# MCU.net
KiCad netlist of a schematic drawn in Altium Designer
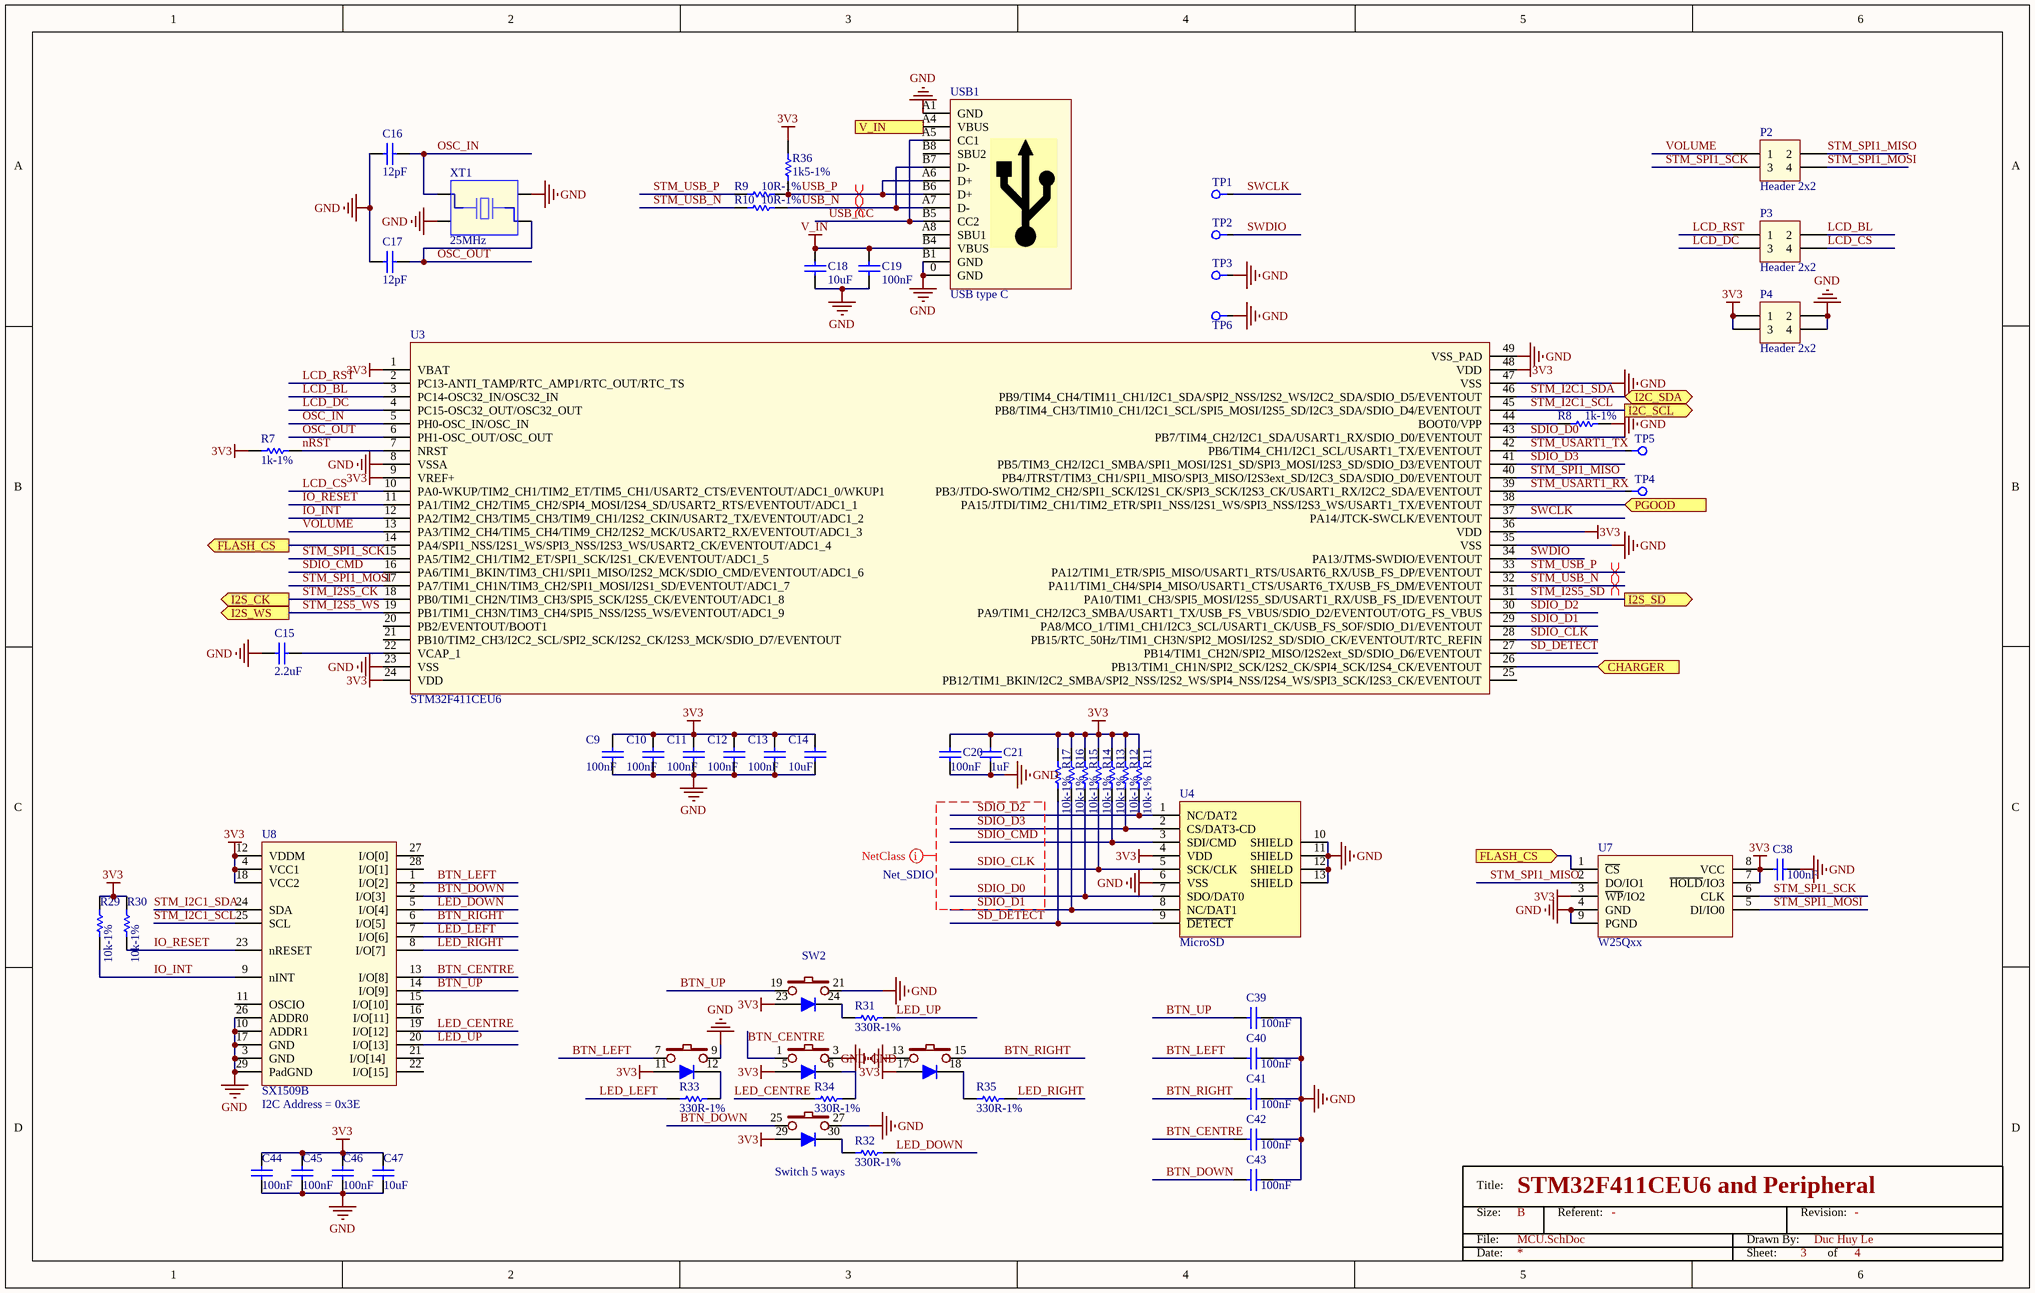
[diagram p0: MCU.SchDoc]

(export (version "E")
  (design (tool "Eeschema 10.0.6"))
  (components
    (comp (ref "C9")
      (value "100nF")
      (footprint "Cap 0603")
      (description "Cap SMD")
      (libsource (lib "duchuylee") (part "Cap"))
    )
    (comp (ref "C10")
      (value "100nF")
      (footprint "Cap 0603")
      (description "Cap SMD")
      (libsource (lib "duchuylee") (part "Cap"))
    )
    (comp (ref "C11")
      (value "100nF")
      (footprint "Cap 0603")
      (description "Cap SMD")
      (libsource (lib "duchuylee") (part "Cap"))
    )
    (comp (ref "C12")
      (value "100nF")
      (footprint "Cap 0603")
      (description "Cap SMD")
      (libsource (lib "duchuylee") (part "Cap"))
    )
    (comp (ref "C13")
      (value "100nF")
      (footprint "Cap 0603")
      (description "Cap SMD")
      (libsource (lib "duchuylee") (part "Cap"))
    )
    (comp (ref "C14")
      (value "10uF")
      (footprint "Cap 0603")
      (description "Cap SMD")
      (libsource (lib "duchuylee") (part "Cap"))
    )
    (comp (ref "C15")
      (value "2.2uF")
      (footprint "Cap 0603")
      (description "Cap SMD")
      (libsource (lib "duchuylee") (part "Cap"))
    )
    (comp (ref "C16")
      (value "12pF")
      (footprint "Cap 0603")
      (description "Cap SMD")
      (libsource (lib "duchuylee") (part "Cap"))
    )
    (comp (ref "C17")
      (value "12pF")
      (footprint "Cap 0603")
      (description "Cap SMD")
      (libsource (lib "duchuylee") (part "Cap"))
    )
    (comp (ref "C18")
      (value "10uF")
      (footprint "Cap 0603")
      (description "Cap SMD")
      (libsource (lib "duchuylee") (part "Cap"))
    )
    (comp (ref "C19")
      (value "100nF")
      (footprint "Cap 0603")
      (description "Cap SMD")
      (libsource (lib "duchuylee") (part "Cap"))
    )
    (comp (ref "C20")
      (value "100nF")
      (footprint "Cap 0603")
      (description "Cap SMD")
      (libsource (lib "duchuylee") (part "Cap"))
    )
    (comp (ref "C21")
      (value "1uF")
      (footprint "Cap 0603")
      (description "Cap SMD")
      (libsource (lib "duchuylee") (part "Cap"))
    )
    (comp (ref "C38")
      (value "100nF")
      (footprint "Cap 0603")
      (description "Cap SMD")
      (libsource (lib "duchuylee") (part "Cap"))
    )
    (comp (ref "C39")
      (value "100nF")
      (footprint "Cap 0603")
      (description "Cap SMD")
      (libsource (lib "duchuylee") (part "Cap"))
    )
    (comp (ref "C40")
      (value "100nF")
      (footprint "Cap 0603")
      (description "Cap SMD")
      (libsource (lib "duchuylee") (part "Cap"))
    )
    (comp (ref "C41")
      (value "100nF")
      (footprint "Cap 0603")
      (description "Cap SMD")
      (libsource (lib "duchuylee") (part "Cap"))
    )
    (comp (ref "C42")
      (value "100nF")
      (footprint "Cap 0603")
      (description "Cap SMD")
      (libsource (lib "duchuylee") (part "Cap"))
    )
    (comp (ref "C43")
      (value "100nF")
      (footprint "Cap 0603")
      (description "Cap SMD")
      (libsource (lib "duchuylee") (part "Cap"))
    )
    (comp (ref "C44")
      (value "100nF")
      (footprint "Cap 0603")
      (description "Cap SMD")
      (libsource (lib "duchuylee") (part "Cap"))
    )
    (comp (ref "C45")
      (value "100nF")
      (footprint "Cap 0603")
      (description "Cap SMD")
      (libsource (lib "duchuylee") (part "Cap"))
    )
    (comp (ref "C46")
      (value "100nF")
      (footprint "Cap 0603")
      (description "Cap SMD")
      (libsource (lib "duchuylee") (part "Cap"))
    )
    (comp (ref "C47")
      (value "10uF")
      (footprint "Cap 0603")
      (description "Cap SMD")
      (libsource (lib "duchuylee") (part "Cap"))
    )
    (comp (ref "P2")
      (value "Header 2x2")
      (footprint "Header 2mm 2x2")
      (libsource (lib "duchuylee") (part "Header 2x2"))
    )
    (comp (ref "P3")
      (value "Header 2x2")
      (footprint "Header 2mm 2x2")
      (libsource (lib "duchuylee") (part "Header 2x2"))
    )
    (comp (ref "P4")
      (value "Header 2x2")
      (footprint "Header 2mm 2x2")
      (libsource (lib "duchuylee") (part "Header 2x2"))
    )
    (comp (ref "R7")
      (value "1k-1%")
      (footprint "Res 0603")
      (description "Res SMD")
      (libsource (lib "duchuylee") (part "Res"))
    )
    (comp (ref "R8")
      (value "1k-1%")
      (footprint "Res 0603")
      (description "Res SMD")
      (libsource (lib "duchuylee") (part "Res"))
    )
    (comp (ref "R9")
      (value "10R-1%")
      (footprint "Res 0603")
      (description "Res SMD")
      (libsource (lib "duchuylee") (part "Res"))
    )
    (comp (ref "R10")
      (value "10R-1%")
      (footprint "Res 0603")
      (description "Res SMD")
      (libsource (lib "duchuylee") (part "Res"))
    )
    (comp (ref "R11")
      (value "10k-1%")
      (footprint "Res 0603")
      (description "Res SMD")
      (libsource (lib "duchuylee") (part "Res"))
    )
    (comp (ref "R12")
      (value "10k-1%")
      (footprint "Res 0603")
      (description "Res SMD")
      (libsource (lib "duchuylee") (part "Res"))
    )
    (comp (ref "R13")
      (value "10k-1%")
      (footprint "Res 0603")
      (description "Res SMD")
      (libsource (lib "duchuylee") (part "Res"))
    )
    (comp (ref "R14")
      (value "10k-1%")
      (footprint "Res 0603")
      (description "Res SMD")
      (libsource (lib "duchuylee") (part "Res"))
    )
    (comp (ref "R15")
      (value "10k-1%")
      (footprint "Res 0603")
      (description "Res SMD")
      (libsource (lib "duchuylee") (part "Res"))
    )
    (comp (ref "R16")
      (value "10k-1%")
      (footprint "Res 0603")
      (description "Res SMD")
      (libsource (lib "duchuylee") (part "Res"))
    )
    (comp (ref "R17")
      (value "10k-1%")
      (footprint "Res 0603")
      (description "Res SMD")
      (libsource (lib "duchuylee") (part "Res"))
    )
    (comp (ref "R29")
      (value "10k-1%")
      (footprint "Res 0603")
      (description "Res SMD")
      (libsource (lib "duchuylee") (part "Res"))
    )
    (comp (ref "R30")
      (value "10k-1%")
      (footprint "Res 0603")
      (description "Res SMD")
      (libsource (lib "duchuylee") (part "Res"))
    )
    (comp (ref "R31")
      (value "330R-1%")
      (footprint "Res 0603")
      (description "Res SMD")
      (libsource (lib "duchuylee") (part "Res"))
    )
    (comp (ref "R32")
      (value "330R-1%")
      (footprint "Res 0603")
      (description "Res SMD")
      (libsource (lib "duchuylee") (part "Res"))
    )
    (comp (ref "R33")
      (value "330R-1%")
      (footprint "Res 0603")
      (description "Res SMD")
      (libsource (lib "duchuylee") (part "Res"))
    )
    (comp (ref "R34")
      (value "330R-1%")
      (footprint "Res 0603")
      (description "Res SMD")
      (libsource (lib "duchuylee") (part "Res"))
    )
    (comp (ref "R35")
      (value "330R-1%")
      (footprint "Res 0603")
      (description "Res SMD")
      (libsource (lib "duchuylee") (part "Res"))
    )
    (comp (ref "R36")
      (value "1k5-1%")
      (footprint "Res 0603")
      (description "Res SMD")
      (libsource (lib "duchuylee") (part "Res"))
    )
    (comp (ref "SW2")
      (value "Switch 5 ways")
      (footprint "Switch 5 ways")
      (description "Switch 5 ways: left, right, up, down, centre")
      (libsource (lib "duchuylee") (part "Switch 5 ways"))
    )
    (comp (ref "TitleBlock3")
      (value "Title Block")
      (fields
        (field (name "REVISION") "-")
        (field (name "TITLE") "STM32F411CEU6 and Peripheral")
        (field (name "REFERENT") "-")
        (field (name "SIZE") "B")
      )
      (libsource (lib "duchuylee") (part "Title Block"))
    )
    (comp (ref "TP1") (value "TP") (footprint "duchuylee:TP") (libsource (lib "duchuylee") (part "TP")))
    (comp (ref "TP2") (value "TP") (footprint "duchuylee:TP") (libsource (lib "duchuylee") (part "TP")))
    (comp (ref "TP3") (value "TP") (footprint "duchuylee:TP") (libsource (lib "duchuylee") (part "TP")))
    (comp (ref "TP4") (value "TP") (footprint "duchuylee:TP") (libsource (lib "duchuylee") (part "TP")))
    (comp (ref "TP5") (value "TP") (footprint "duchuylee:TP") (libsource (lib "duchuylee") (part "TP")))
    (comp (ref "TP6") (value "TP") (footprint "duchuylee:TP") (libsource (lib "duchuylee") (part "TP")))
    (comp (ref "U3")
      (value "STM32F411CEU6")
      (footprint "UFQFPN-48")
      (libsource (lib "duchuylee") (part "STM32F411CEU6"))
    )
    (comp (ref "U4")
      (value "MicroSD")
      (footprint "MicroSD A")
      (description "MicroSD Push-Push A")
      (libsource (lib "duchuylee") (part "MicroSD-A"))
    )
    (comp (ref "U7")
      (value "W25Qxx")
      (footprint "WSON 6x5")
      (description "Flash Memory SPI Interface")
      (libsource (lib "duchuylee") (part "W25Qxx"))
    )
    (comp (ref "U8")
      (value "SX1509B")
      (footprint "QFN-28 4x4")
      (description "SX1509B 16-channel I2C GPIO with LED Driver and Keypad Engine")
      (libsource (lib "duchuylee") (part "SX1509B"))
    )
    (comp (ref "USB1")
      (value "USB type C")
      (footprint "USB Type C")
      (description "USB type C 16 Pins")
      (libsource (lib "duchuylee") (part "USB type C"))
    )
    (comp (ref "XT1")
      (value "25MHz")
      (footprint "Crystal 3225")
      (description "Xtal 4 pins SMD")
      (libsource (lib "duchuylee") (part "XT4"))
    )
  )
  (nets
    (net (code "1") (name "/BTN_CENTRE") (class "Default")
      (node (ref "C42") (pin "2") (pinfunction "2_2") (pintype "passive"))
      (node (ref "SW2") (pin "1") (pinfunction "1_1") (pintype "passive"))
      (node (ref "U8") (pin "13") (pinfunction "I/O[8]_13") (pintype "passive"))
    )
    (net (code "2") (name "/BTN_DOWN") (class "Default")
      (node (ref "C43") (pin "2") (pinfunction "2_2") (pintype "passive"))
      (node (ref "SW2") (pin "25") (pinfunction "25_25") (pintype "passive"))
      (node (ref "U8") (pin "2") (pinfunction "I/O[3]_2") (pintype "passive"))
    )
    (net (code "3") (name "/BTN_LEFT") (class "Default")
      (node (ref "C40") (pin "2") (pinfunction "2_2") (pintype "passive"))
      (node (ref "SW2") (pin "7") (pinfunction "7_7") (pintype "passive"))
      (node (ref "U8") (pin "1") (pinfunction "I/O[2]_1") (pintype "passive"))
    )
    (net (code "4") (name "/BTN_RIGHT") (class "Default")
      (node (ref "C41") (pin "2") (pinfunction "2_2") (pintype "passive"))
      (node (ref "SW2") (pin "15") (pinfunction "15_15") (pintype "passive"))
      (node (ref "U8") (pin "6") (pinfunction "I/O[5]_6") (pintype "passive"))
    )
    (net (code "5") (name "/BTN_UP") (class "Default")
      (node (ref "C39") (pin "2") (pinfunction "2_2") (pintype "passive"))
      (node (ref "SW2") (pin "19") (pinfunction "19_19") (pintype "passive"))
      (node (ref "U8") (pin "14") (pinfunction "I/O[9]_14") (pintype "passive"))
    )
    (net (code "6") (name "/CHARGER") (class "Default")
      (node (ref "U3") (pin "26") (pinfunction "PB13/TIM1_CH1N/SPI2_SCK/I2S2_CK/SPI4_SCK/I2S4_CK/EVENTOUT_26") (pintype "passive"))
    )
    (net (code "7") (name "/FLASH_CS") (class "Default")
      (node (ref "U3") (pin "14") (pinfunction "PA4/SPI1_NSS/I2S1_WS/SPI3_NSS/I2S3_WS/USART2_CK/EVENTOUT/ADC1_4_14") (pintype "passive"))
      (node (ref "U7") (pin "1") (pinfunction "~{CS}_1") (pintype "passive"))
    )
    (net (code "8") (name "/IO_INT") (class "Default")
      (node (ref "R29") (pin "2") (pinfunction "2_2") (pintype "passive"))
      (node (ref "U3") (pin "12") (pinfunction "PA2/TIM2_CH3/TIM5_CH3/TIM9_CH1/I2S2_CKIN/USART2_TX/EVENTOUT/ADC1_2_12") (pintype "passive"))
      (node (ref "U8") (pin "9") (pinfunction "nINT_9") (pintype "passive"))
    )
    (net (code "9") (name "/IO_RESET") (class "Default")
      (node (ref "R30") (pin "2") (pinfunction "2_2") (pintype "passive"))
      (node (ref "U3") (pin "11") (pinfunction "PA1/TIM2_CH2/TIM5_CH2/SPI4_MOSI/I2S4_SD/USART2_RTS/EVENTOUT/ADC1_1_11") (pintype "passive"))
      (node (ref "U8") (pin "23") (pinfunction "nRESET_23") (pintype "passive"))
    )
    (net (code "10") (name "/LCD_BL") (class "Default")
      (node (ref "P3") (pin "2") (pinfunction "2_2") (pintype "passive"))
      (node (ref "U3") (pin "3") (pinfunction "PC14-OSC32_IN/OSC32_IN_3") (pintype "passive"))
    )
    (net (code "11") (name "/LCD_CS") (class "Default")
      (node (ref "P3") (pin "4") (pinfunction "4_4") (pintype "passive"))
      (node (ref "U3") (pin "10") (pinfunction "PA0-WKUP/TIM2_CH1/TIM2_ET/TIM5_CH1/USART2_CTS/EVENTOUT/ADC1_0/WKUP1_10") (pintype "passive"))
    )
    (net (code "12") (name "/LCD_DC") (class "Default")
      (node (ref "P3") (pin "3") (pinfunction "3_3") (pintype "passive"))
      (node (ref "U3") (pin "4") (pinfunction "PC15-OSC32_OUT/OSC32_OUT_4") (pintype "passive"))
    )
    (net (code "13") (name "/LCD_RST") (class "Default")
      (node (ref "P3") (pin "1") (pinfunction "1_1") (pintype "passive"))
      (node (ref "U3") (pin "2") (pinfunction "PC13-ANTI_TAMP/RTC_AMP1/RTC_OUT/RTC_TS_2") (pintype "passive"))
    )
    (net (code "14") (name "/LED_CENTRE") (class "Default")
      (node (ref "R34") (pin "1") (pinfunction "1_1") (pintype "passive"))
      (node (ref "U8") (pin "19") (pinfunction "I/O[12]_19") (pintype "passive"))
    )
    (net (code "15") (name "/LED_DOWN") (class "Default")
      (node (ref "R32") (pin "2") (pinfunction "2_2") (pintype "passive"))
      (node (ref "U8") (pin "5") (pinfunction "I/O[4]_5") (pintype "passive"))
    )
    (net (code "16") (name "/LED_LEFT") (class "Default")
      (node (ref "R33") (pin "1") (pinfunction "1_1") (pintype "passive"))
      (node (ref "U8") (pin "7") (pinfunction "I/O[6]_7") (pintype "passive"))
    )
    (net (code "17") (name "/LED_RIGHT") (class "Default")
      (node (ref "R35") (pin "2") (pinfunction "2_2") (pintype "passive"))
      (node (ref "U8") (pin "8") (pinfunction "I/O[7]_8") (pintype "passive"))
    )
    (net (code "18") (name "/LED_UP") (class "Default")
      (node (ref "R31") (pin "2") (pinfunction "2_2") (pintype "passive"))
      (node (ref "U8") (pin "20") (pinfunction "I/O[13]_20") (pintype "passive"))
    )
    (net (code "19") (name "/OSC_IN") (class "Default")
      (node (ref "C16") (pin "1") (pinfunction "1_1") (pintype "passive"))
      (node (ref "U3") (pin "5") (pinfunction "PH0-OSC_IN/OSC_IN_5") (pintype "passive"))
      (node (ref "XT1") (pin "1") (pinfunction "1_1") (pintype "passive"))
    )
    (net (code "20") (name "/OSC_OUT") (class "Default")
      (node (ref "C17") (pin "1") (pinfunction "1_1") (pintype "passive"))
      (node (ref "U3") (pin "6") (pinfunction "PH1-OSC_OUT/OSC_OUT_6") (pintype "passive"))
      (node (ref "XT1") (pin "3") (pinfunction "3_3") (pintype "passive"))
    )
    (net (code "21") (name "/PGOOD") (class "Default")
      (node (ref "U3") (pin "38") (pinfunction "PA15/JTDI/TIM2_CH1/TIM2_ETR/SPI1_NSS/I2S1_WS/SPI3_NSS/I2S3_WS/USART1_TX/EVENTOUT_38") (pintype "passive"))
    )
    (net (code "22") (name "/SDIO_CLK") (class "Default")
      (node (ref "R14") (pin "2") (pinfunction "2_2") (pintype "passive"))
      (node (ref "U3") (pin "28") (pinfunction "PB15/RTC_50Hz/TIM1_CH3N/SPI2_MOSI/I2S2_SD/SDIO_CK/EVENTOUT/RTC_REFIN_28") (pintype "passive"))
      (node (ref "U4") (pin "5") (pinfunction "SCK/CLK_5") (pintype "passive"))
    )
    (net (code "23") (name "/SDIO_CMD") (class "Default")
      (node (ref "R13") (pin "2") (pinfunction "2_2") (pintype "passive"))
      (node (ref "U3") (pin "16") (pinfunction "PA6/TIM1_BKIN/TIM3_CH1/SPI1_MISO/I2S2_MCK/SDIO_CMD/EVENTOUT/ADC1_6_16") (pintype "passive"))
      (node (ref "U4") (pin "3") (pinfunction "SDI/CMD_3") (pintype "passive"))
    )
    (net (code "24") (name "/SDIO_D0") (class "Default")
      (node (ref "R15") (pin "2") (pinfunction "2_2") (pintype "passive"))
      (node (ref "U3") (pin "43") (pinfunction "PB7/TIM4_CH2/I2C1_SDA/USART1_RX/SDIO_D0/EVENTOUT_43") (pintype "passive"))
      (node (ref "U4") (pin "7") (pinfunction "SDO/DAT0_7") (pintype "passive"))
    )
    (net (code "25") (name "/SDIO_D1") (class "Default")
      (node (ref "R16") (pin "2") (pinfunction "2_2") (pintype "passive"))
      (node (ref "U3") (pin "29") (pinfunction "PA8/MCO_1/TIM1_CH1/I2C3_SCL/USART1_CK/USB_FS_SOF/SDIO_D1/EVENTOUT_29") (pintype "passive"))
      (node (ref "U4") (pin "8") (pinfunction "NC/DAT1_8") (pintype "passive"))
    )
    (net (code "26") (name "/SDIO_D2") (class "Default")
      (node (ref "R11") (pin "2") (pinfunction "2_2") (pintype "passive"))
      (node (ref "U3") (pin "30") (pinfunction "PA9/TIM1_CH2/I2C3_SMBA/USART1_TX/USB_FS_VBUS/SDIO_D2/EVENTOUT/OTG_FS_VBUS_30") (pintype "passive"))
      (node (ref "U4") (pin "1") (pinfunction "NC/DAT2_1") (pintype "passive"))
    )
    (net (code "27") (name "/SDIO_D3") (class "Default")
      (node (ref "R12") (pin "2") (pinfunction "2_2") (pintype "passive"))
      (node (ref "U3") (pin "41") (pinfunction "PB5/TIM3_CH2/I2C1_SMBA/SPI1_MOSI/I2S1_SD/SPI3_MOSI/I2S3_SD/SDIO_D3/EVENTOUT_41") (pintype "passive"))
      (node (ref "U4") (pin "2") (pinfunction "CS/DAT3-CD_2") (pintype "passive"))
    )
    (net (code "28") (name "/SD_DETECT") (class "Default")
      (node (ref "R17") (pin "2") (pinfunction "2_2") (pintype "passive"))
      (node (ref "U3") (pin "27") (pinfunction "PB14/TIM1_CH2N/SPI2_MISO/I2S2ext_SD/SDIO_D6/EVENTOUT_27") (pintype "passive"))
      (node (ref "U4") (pin "9") (pinfunction "~{DETECT}_9") (pintype "passive"))
    )
    (net (code "29") (name "/STM_I2C1_SCL") (class "Default")
      (node (ref "U3") (pin "45") (pinfunction "PB8/TIM4_CH3/TIM10_CH1/I2C1_SCL/SPI5_MOSI/I2S5_SD/I2C3_SDA/SDIO_D4/EVENTOUT_45") (pintype "passive"))
      (node (ref "U8") (pin "25") (pinfunction "SCL_25") (pintype "passive"))
    )
    (net (code "30") (name "/STM_I2C1_SDA") (class "Default")
      (node (ref "U3") (pin "46") (pinfunction "PB9/TIM4_CH4/TIM11_CH1/I2C1_SDA/SPI2_NSS/I2S2_WS/I2C2_SDA/SDIO_D5/EVENTOUT_46") (pintype "passive"))
      (node (ref "U8") (pin "24") (pinfunction "SDA_24") (pintype "passive"))
    )
    (net (code "31") (name "/STM_I2S5_CK") (class "Default")
      (node (ref "U3") (pin "18") (pinfunction "PB0/TIM1_CH2N/TIM3_CH3/SPI5_SCK/I2S5_CK/EVENTOUT/ADC1_8_18") (pintype "passive"))
    )
    (net (code "32") (name "/STM_I2S5_SD") (class "Default")
      (node (ref "U3") (pin "31") (pinfunction "PA10/TIM1_CH3/SPI5_MOSI/I2S5_SD/USART1_RX/USB_FS_ID/EVENTOUT_31") (pintype "passive"))
    )
    (net (code "33") (name "/STM_I2S5_WS") (class "Default")
      (node (ref "U3") (pin "19") (pinfunction "PB1/TIM1_CH3N/TIM3_CH4/SPI5_NSS/I2S5_WS/EVENTOUT/ADC1_9_19") (pintype "passive"))
    )
    (net (code "34") (name "/STM_SPI1_MISO") (class "Default")
      (node (ref "P2") (pin "2") (pinfunction "2_2") (pintype "passive"))
      (node (ref "U3") (pin "40") (pinfunction "PB4/JTRST/TIM3_CH1/SPI1_MISO/SPI3_MISO/I2S3ext_SD/I2C3_SDA/SDIO_D0/EVENTOUT_40") (pintype "passive"))
      (node (ref "U7") (pin "2") (pinfunction "DO/IO1_2") (pintype "passive"))
    )
    (net (code "35") (name "/STM_SPI1_MOSI") (class "Default")
      (node (ref "P2") (pin "4") (pinfunction "4_4") (pintype "passive"))
      (node (ref "U3") (pin "17") (pinfunction "PA7/TIM1_CH1N/TIM3_CH2/SPI1_MOSI/I2S1_SD/EVENTOUT/ADC1_7_17") (pintype "passive"))
      (node (ref "U7") (pin "5") (pinfunction "DI/IO0_5") (pintype "passive"))
    )
    (net (code "36") (name "/STM_SPI1_SCK") (class "Default")
      (node (ref "P2") (pin "3") (pinfunction "3_3") (pintype "passive"))
      (node (ref "U3") (pin "15") (pinfunction "PA5/TIM2_CH1/TIM2_ET/SPI1_SCK/I2S1_CK/EVENTOUT/ADC1_5_15") (pintype "passive"))
      (node (ref "U7") (pin "6") (pinfunction "CLK_6") (pintype "passive"))
    )
    (net (code "37") (name "/STM_USART1_RX") (class "Default")
      (node (ref "TP4") (pin "1") (pinfunction "1_1") (pintype "passive"))
      (node (ref "U3") (pin "39") (pinfunction "PB3/JTDO-SWO/TIM2_CH2/SPI1_SCK/I2S1_CK/SPI3_SCK/I2S3_CK/USART1_RX/I2C2_SDA/EVENTOUT_39") (pintype "passive"))
    )
    (net (code "38") (name "/STM_USART1_TX") (class "Default")
      (node (ref "TP5") (pin "1") (pinfunction "1_1") (pintype "passive"))
      (node (ref "U3") (pin "42") (pinfunction "PB6/TIM4_CH1/I2C1_SCL/USART1_TX/EVENTOUT_42") (pintype "passive"))
    )
    (net (code "39") (name "/STM_USB_N") (class "Default")
      (node (ref "R10") (pin "2") (pinfunction "2_2") (pintype "passive"))
      (node (ref "U3") (pin "32") (pinfunction "PA11/TIM1_CH4/SPI4_MISO/USART1_CTS/USART6_TX/USB_FS_DM/EVENTOUT_32") (pintype "passive"))
    )
    (net (code "40") (name "/STM_USB_P") (class "Default")
      (node (ref "R9") (pin "2") (pinfunction "2_2") (pintype "passive"))
      (node (ref "U3") (pin "33") (pinfunction "PA12/TIM1_ETR/SPI5_MISO/USART1_RTS/USART6_RX/USB_FS_DP/EVENTOUT_33") (pintype "passive"))
    )
    (net (code "41") (name "/SWCLK") (class "Default")
      (node (ref "TP1") (pin "1") (pinfunction "1_1") (pintype "passive"))
      (node (ref "U3") (pin "37") (pinfunction "PA14/JTCK-SWCLK/EVENTOUT_37") (pintype "passive"))
    )
    (net (code "42") (name "/SWDIO") (class "Default")
      (node (ref "TP2") (pin "1") (pinfunction "1_1") (pintype "passive"))
      (node (ref "U3") (pin "34") (pinfunction "PA13/JTMS-SWDIO/EVENTOUT_34") (pintype "passive"))
    )
    (net (code "43") (name "/USB_CC") (class "Default")
      (node (ref "USB1") (pin "A5") (pinfunction "CC1_A5") (pintype "passive"))
      (node (ref "USB1") (pin "B5") (pinfunction "CC2_B5") (pintype "passive"))
    )
    (net (code "44") (name "/USB_N") (class "Default")
      (node (ref "R10") (pin "1") (pinfunction "1_1") (pintype "passive"))
      (node (ref "USB1") (pin "A7") (pinfunction "D-_A7") (pintype "passive"))
      (node (ref "USB1") (pin "B7") (pinfunction "D-_B7") (pintype "passive"))
    )
    (net (code "45") (name "/USB_P") (class "Default")
      (node (ref "R36") (pin "1") (pinfunction "1_1") (pintype "passive"))
      (node (ref "R9") (pin "1") (pinfunction "1_1") (pintype "passive"))
      (node (ref "USB1") (pin "A6") (pinfunction "D+_A6") (pintype "passive"))
      (node (ref "USB1") (pin "B6") (pinfunction "D+_B6") (pintype "passive"))
    )
    (net (code "46") (name "/VOLUME") (class "Default")
      (node (ref "P2") (pin "1") (pinfunction "1_1") (pintype "passive"))
      (node (ref "U3") (pin "13") (pinfunction "PA3/TIM2_CH4/TIM5_CH4/TIM9_CH2/I2S2_MCK/USART2_RX/EVENTOUT/ADC1_3_13") (pintype "passive"))
    )
    (net (code "47") (name "/nRST") (class "Default")
      (node (ref "R7") (pin "1") (pinfunction "1_1") (pintype "passive"))
      (node (ref "U3") (pin "7") (pinfunction "NRST_7") (pintype "passive"))
    )
    (net (code "48") (name "3V3") (class "Default")
      (node (ref "C10") (pin "2") (pinfunction "2_2") (pintype "passive"))
      (node (ref "C11") (pin "2") (pinfunction "2_2") (pintype "passive"))
      (node (ref "C12") (pin "2") (pinfunction "2_2") (pintype "passive"))
      (node (ref "C13") (pin "2") (pinfunction "2_2") (pintype "passive"))
      (node (ref "C14") (pin "2") (pinfunction "2_2") (pintype "passive"))
      (node (ref "C20") (pin "1") (pinfunction "1_1") (pintype "passive"))
      (node (ref "C21") (pin "1") (pinfunction "1_1") (pintype "passive"))
      (node (ref "C38") (pin "2") (pinfunction "2_2") (pintype "passive"))
      (node (ref "C44") (pin "2") (pinfunction "2_2") (pintype "passive"))
      (node (ref "C45") (pin "2") (pinfunction "2_2") (pintype "passive"))
      (node (ref "C46") (pin "2") (pinfunction "2_2") (pintype "passive"))
      (node (ref "C47") (pin "2") (pinfunction "2_2") (pintype "passive"))
      (node (ref "C9") (pin "2") (pinfunction "2_2") (pintype "passive"))
      (node (ref "P4") (pin "1") (pinfunction "1_1") (pintype "passive"))
      (node (ref "P4") (pin "3") (pinfunction "3_3") (pintype "passive"))
      (node (ref "R11") (pin "1") (pinfunction "1_1") (pintype "passive"))
      (node (ref "R12") (pin "1") (pinfunction "1_1") (pintype "passive"))
      (node (ref "R13") (pin "1") (pinfunction "1_1") (pintype "passive"))
      (node (ref "R14") (pin "1") (pinfunction "1_1") (pintype "passive"))
      (node (ref "R15") (pin "1") (pinfunction "1_1") (pintype "passive"))
      (node (ref "R16") (pin "1") (pinfunction "1_1") (pintype "passive"))
      (node (ref "R17") (pin "1") (pinfunction "1_1") (pintype "passive"))
      (node (ref "R29") (pin "1") (pinfunction "1_1") (pintype "passive"))
      (node (ref "R30") (pin "1") (pinfunction "1_1") (pintype "passive"))
      (node (ref "R36") (pin "2") (pinfunction "2_2") (pintype "passive"))
      (node (ref "R7") (pin "2") (pinfunction "2_2") (pintype "passive"))
      (node (ref "SW2") (pin "11") (pinfunction "A_11") (pintype "passive"))
      (node (ref "SW2") (pin "17") (pinfunction "A_17") (pintype "passive"))
      (node (ref "SW2") (pin "23") (pinfunction "A_23") (pintype "passive"))
      (node (ref "SW2") (pin "29") (pinfunction "A_29") (pintype "passive"))
      (node (ref "SW2") (pin "5") (pinfunction "A_5") (pintype "passive"))
      (node (ref "U3") (pin "1") (pinfunction "VBAT_1") (pintype "passive"))
      (node (ref "U3") (pin "24") (pinfunction "VDD_24") (pintype "passive"))
      (node (ref "U3") (pin "36") (pinfunction "VDD_36") (pintype "passive"))
      (node (ref "U3") (pin "48") (pinfunction "VDD_48") (pintype "passive"))
      (node (ref "U3") (pin "9") (pinfunction "VREF+_9") (pintype "passive"))
      (node (ref "U4") (pin "4") (pinfunction "VDD_4") (pintype "passive"))
      (node (ref "U7") (pin "3") (pinfunction "~{WP}/IO2_3") (pintype "passive"))
      (node (ref "U7") (pin "7") (pinfunction "~{HOLD}/IO3_7") (pintype "passive"))
      (node (ref "U7") (pin "8") (pinfunction "VCC_8") (pintype "passive"))
      (node (ref "U8") (pin "12") (pinfunction "VDDM_12") (pintype "passive"))
      (node (ref "U8") (pin "18") (pinfunction "VCC2_18") (pintype "passive"))
      (node (ref "U8") (pin "4") (pinfunction "VCC1_4") (pintype "passive"))
    )
    (net (code "49") (name "GND") (class "Default")
      (node (ref "C10") (pin "1") (pinfunction "1_1") (pintype "passive"))
      (node (ref "C11") (pin "1") (pinfunction "1_1") (pintype "passive"))
      (node (ref "C12") (pin "1") (pinfunction "1_1") (pintype "passive"))
      (node (ref "C13") (pin "1") (pinfunction "1_1") (pintype "passive"))
      (node (ref "C14") (pin "1") (pinfunction "1_1") (pintype "passive"))
      (node (ref "C15") (pin "2") (pinfunction "2_2") (pintype "passive"))
      (node (ref "C16") (pin "2") (pinfunction "2_2") (pintype "passive"))
      (node (ref "C17") (pin "2") (pinfunction "2_2") (pintype "passive"))
      (node (ref "C18") (pin "2") (pinfunction "2_2") (pintype "passive"))
      (node (ref "C19") (pin "2") (pinfunction "2_2") (pintype "passive"))
      (node (ref "C20") (pin "2") (pinfunction "2_2") (pintype "passive"))
      (node (ref "C21") (pin "2") (pinfunction "2_2") (pintype "passive"))
      (node (ref "C38") (pin "1") (pinfunction "1_1") (pintype "passive"))
      (node (ref "C39") (pin "1") (pinfunction "1_1") (pintype "passive"))
      (node (ref "C40") (pin "1") (pinfunction "1_1") (pintype "passive"))
      (node (ref "C41") (pin "1") (pinfunction "1_1") (pintype "passive"))
      (node (ref "C42") (pin "1") (pinfunction "1_1") (pintype "passive"))
      (node (ref "C43") (pin "1") (pinfunction "1_1") (pintype "passive"))
      (node (ref "C44") (pin "1") (pinfunction "1_1") (pintype "passive"))
      (node (ref "C45") (pin "1") (pinfunction "1_1") (pintype "passive"))
      (node (ref "C46") (pin "1") (pinfunction "1_1") (pintype "passive"))
      (node (ref "C47") (pin "1") (pinfunction "1_1") (pintype "passive"))
      (node (ref "C9") (pin "1") (pinfunction "1_1") (pintype "passive"))
      (node (ref "P4") (pin "2") (pinfunction "2_2") (pintype "passive"))
      (node (ref "P4") (pin "4") (pinfunction "4_4") (pintype "passive"))
      (node (ref "R8") (pin "1") (pinfunction "1_1") (pintype "passive"))
      (node (ref "SW2") (pin "13") (pinfunction "13_13") (pintype "passive"))
      (node (ref "SW2") (pin "21") (pinfunction "21_21") (pintype "passive"))
      (node (ref "SW2") (pin "27") (pinfunction "27_27") (pintype "passive"))
      (node (ref "SW2") (pin "3") (pinfunction "3_3") (pintype "passive"))
      (node (ref "SW2") (pin "9") (pinfunction "9_9") (pintype "passive"))
      (node (ref "TP3") (pin "1") (pinfunction "1_1") (pintype "passive"))
      (node (ref "TP6") (pin "1") (pinfunction "1_1") (pintype "passive"))
      (node (ref "U3") (pin "23") (pinfunction "VSS_23") (pintype "passive"))
      (node (ref "U3") (pin "35") (pinfunction "VSS_35") (pintype "passive"))
      (node (ref "U3") (pin "47") (pinfunction "VSS_47") (pintype "passive"))
      (node (ref "U3") (pin "49") (pinfunction "VSS_PAD_49") (pintype "passive"))
      (node (ref "U3") (pin "8") (pinfunction "VSSA_8") (pintype "passive"))
      (node (ref "U4") (pin "10") (pinfunction "SHIELD_10") (pintype "passive"))
      (node (ref "U4") (pin "11") (pinfunction "SHIELD_11") (pintype "passive"))
      (node (ref "U4") (pin "12") (pinfunction "SHIELD_12") (pintype "passive"))
      (node (ref "U4") (pin "13") (pinfunction "SHIELD_13") (pintype "passive"))
      (node (ref "U4") (pin "6") (pinfunction "VSS_6") (pintype "passive"))
      (node (ref "U7") (pin "4") (pinfunction "GND_4") (pintype "passive"))
      (node (ref "U7") (pin "9") (pinfunction "PGND_9") (pintype "passive"))
      (node (ref "U8") (pin "10") (pinfunction "ADDR1_10") (pintype "passive"))
      (node (ref "U8") (pin "17") (pinfunction "GND_17") (pintype "passive"))
      (node (ref "U8") (pin "26") (pinfunction "ADDR0_26") (pintype "passive"))
      (node (ref "U8") (pin "29") (pinfunction "PadGND_29") (pintype "passive"))
      (node (ref "U8") (pin "3") (pinfunction "GND_3") (pintype "passive"))
      (node (ref "USB1") (pin "0") (pinfunction "GND_0") (pintype "passive"))
      (node (ref "USB1") (pin "A1") (pinfunction "GND_A1") (pintype "passive"))
      (node (ref "USB1") (pin "B1") (pinfunction "GND_B1") (pintype "passive"))
      (node (ref "XT1") (pin "2") (pinfunction "2_2") (pintype "passive"))
      (node (ref "XT1") (pin "4") (pinfunction "4_4") (pintype "passive"))
    )
    (net (code "50") (name "Net-(R31-Pad1)") (class "Default")
      (node (ref "R31") (pin "1") (pinfunction "1_1") (pintype "passive"))
      (node (ref "SW2") (pin "24") (pinfunction "K_24") (pintype "passive"))
    )
    (net (code "51") (name "Net-(R32-Pad1)") (class "Default")
      (node (ref "R32") (pin "1") (pinfunction "1_1") (pintype "passive"))
      (node (ref "SW2") (pin "30") (pinfunction "K_30") (pintype "passive"))
    )
    (net (code "52") (name "Net-(R33-Pad2)") (class "Default")
      (node (ref "R33") (pin "2") (pinfunction "2_2") (pintype "passive"))
      (node (ref "SW2") (pin "12") (pinfunction "K_12") (pintype "passive"))
    )
    (net (code "53") (name "Net-(R34-Pad2)") (class "Default")
      (node (ref "R34") (pin "2") (pinfunction "2_2") (pintype "passive"))
      (node (ref "SW2") (pin "6") (pinfunction "K_6") (pintype "passive"))
    )
    (net (code "54") (name "Net-(R35-Pad1)") (class "Default")
      (node (ref "R35") (pin "1") (pinfunction "1_1") (pintype "passive"))
      (node (ref "SW2") (pin "18") (pinfunction "K_18") (pintype "passive"))
    )
    (net (code "55") (name "Net-(U3-BOOT0{slash}VPP)") (class "Default")
      (node (ref "R8") (pin "2") (pinfunction "2_2") (pintype "passive"))
      (node (ref "U3") (pin "44") (pinfunction "BOOT0/VPP_44") (pintype "passive"))
    )
    (net (code "56") (name "Net-(U3-VCAP_1)") (class "Default")
      (node (ref "C15") (pin "1") (pinfunction "1_1") (pintype "passive"))
      (node (ref "U3") (pin "22") (pinfunction "VCAP_1_22") (pintype "passive"))
    )
    (net (code "57") (name "V_IN") (class "Default")
      (node (ref "C18") (pin "1") (pinfunction "1_1") (pintype "passive"))
      (node (ref "C19") (pin "1") (pinfunction "1_1") (pintype "passive"))
      (node (ref "USB1") (pin "A4") (pinfunction "VBUS_A4") (pintype "passive"))
      (node (ref "USB1") (pin "B4") (pinfunction "VBUS_B4") (pintype "passive"))
    )
    (net (code "58") (name "unconnected-(U3-PB2{slash}EVENTOUT{slash}BOOT1-Pad20)") (class "Default")
      (node (ref "U3") (pin "20") (pinfunction "PB2/EVENTOUT/BOOT1_20") (pintype "passive"))
    )
    (net (code "59") (name "unconnected-(U3-PB10{slash}TIM2_CH3{slash}I2C2_SCL{slash}SPI2_SCK{slash}I2S2_CK{slash}I2S3_MCK{slash}SDIO_D7{slash}EVENTOUT-Pad21)") (class "Default")
      (node (ref "U3") (pin "21") (pinfunction "PB10/TIM2_CH3/I2C2_SCL/SPI2_SCK/I2S2_CK/I2S3_MCK/SDIO_D7/EVENTOUT_21") (pintype "passive"))
    )
    (net (code "60") (name "unconnected-(U3-PB12{slash}TIM1_BKIN{slash}I2C2_SMBA{slash}SPI2_NSS{slash}I2S2_WS{slash}SPI4_NSS{slash}I2S4_WS{slash}SPI3_SCK{slash}I2S3_CK{slash}EVENTOUT-Pad25)") (class "Default")
      (node (ref "U3") (pin "25") (pinfunction "PB12/TIM1_BKIN/I2C2_SMBA/SPI2_NSS/I2S2_WS/SPI4_NSS/I2S4_WS/SPI3_SCK/I2S3_CK/EVENTOUT_25") (pintype "passive"))
    )
    (net (code "61") (name "unconnected-(U8-I{slash}O[0]-Pad27)") (class "Default")
      (node (ref "U8") (pin "27") (pinfunction "I/O[0]_27") (pintype "passive"))
    )
    (net (code "62") (name "unconnected-(U8-I{slash}O[1]-Pad28)") (class "Default")
      (node (ref "U8") (pin "28") (pinfunction "I/O[1]_28") (pintype "passive"))
    )
    (net (code "63") (name "unconnected-(U8-I{slash}O[10]-Pad15)") (class "Default")
      (node (ref "U8") (pin "15") (pinfunction "I/O[10]_15") (pintype "passive"))
    )
    (net (code "64") (name "unconnected-(U8-I{slash}O[11]-Pad16)") (class "Default")
      (node (ref "U8") (pin "16") (pinfunction "I/O[11]_16") (pintype "passive"))
    )
    (net (code "65") (name "unconnected-(U8-I{slash}O[14]-Pad21)") (class "Default")
      (node (ref "U8") (pin "21") (pinfunction "I/O[14]_21") (pintype "passive"))
    )
    (net (code "66") (name "unconnected-(U8-I{slash}O[15]-Pad22)") (class "Default")
      (node (ref "U8") (pin "22") (pinfunction "I/O[15]_22") (pintype "passive"))
    )
    (net (code "67") (name "unconnected-(U8-OSCIO-Pad11)") (class "Default")
      (node (ref "U8") (pin "11") (pinfunction "OSCIO_11") (pintype "passive"))
    )
    (net (code "68") (name "unconnected-(USB1-SBU1-PadA8)") (class "Default")
      (node (ref "USB1") (pin "A8") (pinfunction "SBU1_A8") (pintype "passive"))
    )
    (net (code "69") (name "unconnected-(USB1-SBU2-PadB8)") (class "Default")
      (node (ref "USB1") (pin "B8") (pinfunction "SBU2_B8") (pintype "passive"))
    )
  )
)
